# Heracles_Headers.net
KiCad netlist of a schematic drawn in Altium Designer
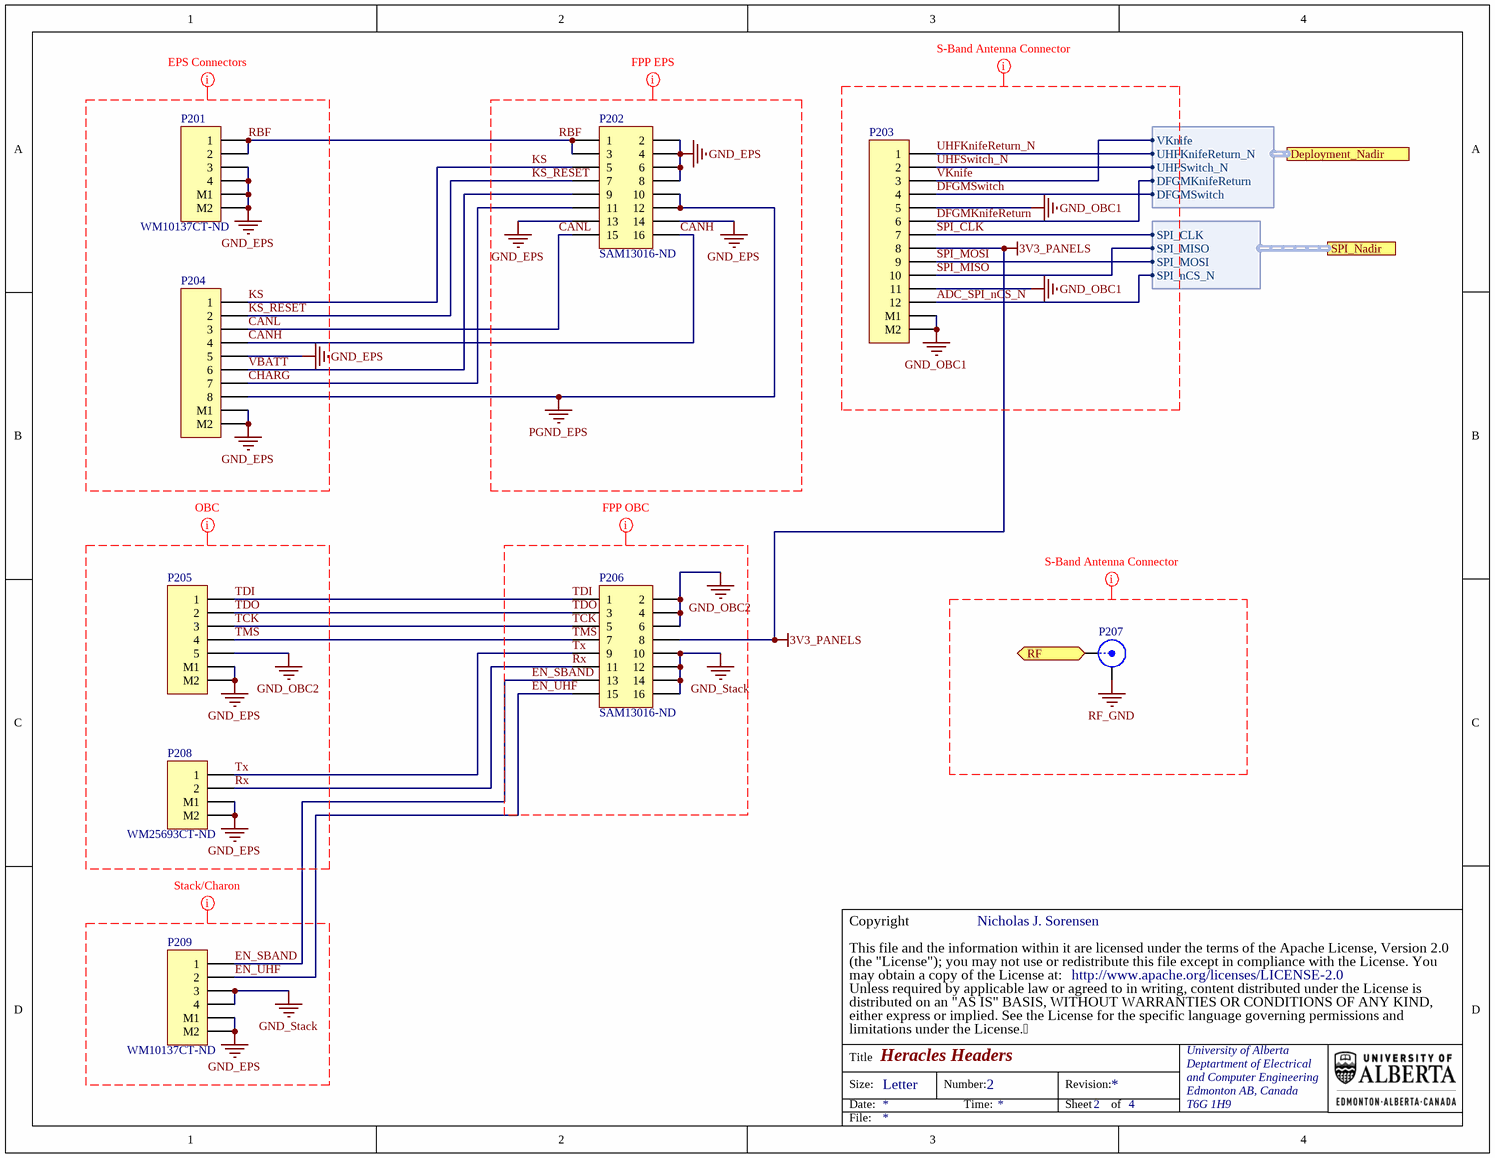
[diagram p0: Heracles Headers.SchDoc]

(export (version "E")
  (design (tool "Eeschema 10.0.6"))
  (components
    (comp (ref "P201")
      (value "WM10137CT-ND")
      (footprint "MOLX-5040500491")
      (description "CONN HEADER SMD R/A 4POS 1.5MM")
      (fields
        (field (name "PART NUMBER") "63")
        (field (name "MANUFACTURER PART NUMBER") "5040500491")
        (field (name "PUBLISHER") "Altium Limited")
      )
      (libsource (lib "Database") (part "Header 6"))
    )
    (comp (ref "P202")
      (value "SAM13016-ND")
      (footprint "TSS-108-01-G-D")
      (description "CONN HEADER VERT 16POS 2.54MM")
      (fields
        (field (name "PART NUMBER") "PP-SAM-00007")
        (field (name "MANUFACTURER PART NUMBER") "TSS-108-01-G-D")
        (field (name "PUBLISHER") "AlbertaSat")
      )
      (libsource (lib "Database") (part "Header 8X2"))
    )
    (comp (ref "P203")
      (value "PICOLOCK 12")
      (footprint "MOLX-5040501291")
      (description "CONN HEADER SMD R/A 12POS 1.5MM")
      (fields
        (field (name "PART NUMBER") "71")
        (field (name "MANUFACTURER PART NUMBER") "5040501291")
        (field (name "PUBLISHER") "Altium Limited")
      )
      (libsource (lib "Database") (part "Header 14"))
    )
    (comp (ref "P204")
      (value "WM14421CT-ND")
      (footprint "MOLX-5040500891")
      (description "CONN HEADER SMD R/A 8POS 1.5MM")
      (fields
        (field (name "PART NUMBER") "67")
        (field (name "MANUFACTURER PART NUMBER") "5040500891")
        (field (name "PUBLISHER") "Altium Limited")
      )
      (libsource (lib "Database") (part "Header 10"))
    )
    (comp (ref "P205")
      (value "PICOLOCK 5")
      (footprint "MOLX-5040500591")
      (description "CONN HEADER SMD R/A 5POS 1.5MM")
      (fields
        (field (name "PART NUMBER") "64")
        (field (name "MANUFACTURER PART NUMBER") "5040500591")
        (field (name "PUBLISHER") "Altium Limited")
      )
      (libsource (lib "Database") (part "Header 7"))
    )
    (comp (ref "P206")
      (value "SAM13016-ND")
      (footprint "TSS-108-01-G-D")
      (description "CONN HEADER VERT 16POS 2.54MM")
      (fields
        (field (name "PART NUMBER") "PP-SAM-00007")
        (field (name "MANUFACTURER PART NUMBER") "TSS-108-01-G-D")
        (field (name "PUBLISHER") "AlbertaSat")
      )
      (libsource (lib "Database") (part "Header 8X2"))
    )
    (comp (ref "P207")
      (value "J10399-ND")
      (footprint "J10399-ND")
      (description "CONN SMB PLUG R/A 50OHM PCB")
      (fields
        (field (name "PART NUMBER") "P01-CIN-00000")
        (field (name "MANUFACTURER PART NUMBER") "Cinch Connectivity Solutions Johnson")
        (field (name "PUBLISHER") "AlbertaSat")
      )
      (libsource (lib "Database") (part "SMB"))
    )
    (comp (ref "P208")
      (value "WM25693CT-ND")
      (footprint "MOLX-5040500291")
      (description "CONN HEADER SMD R/A 2POS 1.5MM")
      (fields
        (field (name "PART NUMBER") "61")
        (field (name "MANUFACTURER PART NUMBER") "5040500291")
        (field (name "PUBLISHER") "Altium Limited")
      )
      (libsource (lib "Database") (part "Header 4"))
    )
    (comp (ref "P209")
      (value "WM10137CT-ND")
      (footprint "MOLX-5040500491")
      (description "CONN HEADER SMD R/A 4POS 1.5MM")
      (fields
        (field (name "PART NUMBER") "63")
        (field (name "MANUFACTURER PART NUMBER") "5040500491")
        (field (name "PUBLISHER") "Altium Limited")
      )
      (libsource (lib "Database") (part "Header 6"))
    )
  )
  (nets
    (net (code "3") (name "/ADC_SPI_nCS_N") (class "Default")
      (node (ref "P203") (pin "12") (pinfunction "12_12") (pintype "passive"))
    )
    (net (code "4") (name "/CANH") (class "Default")
      (node (ref "P202") (pin "16") (pinfunction "16_16") (pintype "passive"))
      (node (ref "P204") (pin "4") (pinfunction "4_4") (pintype "passive"))
    )
    (net (code "5") (name "/CANL") (class "Default")
      (node (ref "P202") (pin "15") (pinfunction "15_15") (pintype "passive"))
      (node (ref "P204") (pin "3") (pinfunction "3_3") (pintype "passive"))
    )
    (net (code "6") (name "/CHARG") (class "Default")
      (node (ref "P202") (pin "11") (pinfunction "11_11") (pintype "passive"))
      (node (ref "P204") (pin "7") (pinfunction "7_7") (pintype "passive"))
    )
    (net (code "7") (name "/DFGMKnifeReturn") (class "Default")
      (node (ref "P203") (pin "6") (pinfunction "6_6") (pintype "passive"))
    )
    (net (code "8") (name "/DFGMSwitch") (class "Default")
      (node (ref "P203") (pin "4") (pinfunction "4_4") (pintype "passive"))
    )
    (net (code "9") (name "/EN_SBAND") (class "Default")
      (node (ref "P206") (pin "13") (pinfunction "13_13") (pintype "passive"))
      (node (ref "P209") (pin "1") (pinfunction "1_1") (pintype "passive"))
    )
    (net (code "10") (name "/EN_UHF") (class "Default")
      (node (ref "P206") (pin "15") (pinfunction "15_15") (pintype "passive"))
      (node (ref "P209") (pin "2") (pinfunction "2_2") (pintype "passive"))
    )
    (net (code "11") (name "/KS") (class "Default")
      (node (ref "P202") (pin "5") (pinfunction "5_5") (pintype "passive"))
      (node (ref "P204") (pin "1") (pinfunction "1_1") (pintype "passive"))
    )
    (net (code "12") (name "/KS_RESET") (class "Default")
      (node (ref "P202") (pin "7") (pinfunction "7_7") (pintype "passive"))
      (node (ref "P204") (pin "2") (pinfunction "2_2") (pintype "passive"))
    )
    (net (code "13") (name "/RBF") (class "Default")
      (node (ref "P201") (pin "1") (pinfunction "1_1") (pintype "passive"))
      (node (ref "P201") (pin "2") (pinfunction "2_2") (pintype "passive"))
      (node (ref "P202") (pin "1") (pinfunction "1_1") (pintype "passive"))
      (node (ref "P202") (pin "3") (pinfunction "3_3") (pintype "passive"))
    )
    (net (code "14") (name "/RF") (class "Default")
      (node (ref "P207") (pin "1") (pinfunction "X_1") (pintype "passive"))
    )
    (net (code "15") (name "/Rx") (class "Default")
      (node (ref "P206") (pin "11") (pinfunction "11_11") (pintype "passive"))
      (node (ref "P208") (pin "2") (pinfunction "2_2") (pintype "passive"))
    )
    (net (code "16") (name "/SPI_CLK") (class "Default")
      (node (ref "P203") (pin "7") (pinfunction "7_7") (pintype "passive"))
    )
    (net (code "17") (name "/SPI_MISO") (class "Default")
      (node (ref "P203") (pin "10") (pinfunction "10_10") (pintype "passive"))
    )
    (net (code "18") (name "/SPI_MOSI") (class "Default")
      (node (ref "P203") (pin "9") (pinfunction "9_9") (pintype "passive"))
    )
    (net (code "19") (name "/TCK") (class "Default")
      (node (ref "P205") (pin "3") (pinfunction "3_3") (pintype "passive"))
      (node (ref "P206") (pin "5") (pinfunction "5_5") (pintype "passive"))
    )
    (net (code "20") (name "/TDI") (class "Default")
      (node (ref "P205") (pin "1") (pinfunction "1_1") (pintype "passive"))
      (node (ref "P206") (pin "1") (pinfunction "1_1") (pintype "passive"))
    )
    (net (code "21") (name "/TDO") (class "Default")
      (node (ref "P205") (pin "2") (pinfunction "2_2") (pintype "passive"))
      (node (ref "P206") (pin "3") (pinfunction "3_3") (pintype "passive"))
    )
    (net (code "22") (name "/TMS") (class "Default")
      (node (ref "P205") (pin "4") (pinfunction "4_4") (pintype "passive"))
      (node (ref "P206") (pin "7") (pinfunction "7_7") (pintype "passive"))
    )
    (net (code "23") (name "/Tx") (class "Default")
      (node (ref "P206") (pin "9") (pinfunction "9_9") (pintype "passive"))
      (node (ref "P208") (pin "1") (pinfunction "1_1") (pintype "passive"))
    )
    (net (code "24") (name "/UHFKnifeReturn_N") (class "Default")
      (node (ref "P203") (pin "1") (pinfunction "1_1") (pintype "passive"))
    )
    (net (code "25") (name "/UHFSwitch_N") (class "Default")
      (node (ref "P203") (pin "2") (pinfunction "2_2") (pintype "passive"))
    )
    (net (code "26") (name "/VBATT") (class "Default")
      (node (ref "P202") (pin "9") (pinfunction "9_9") (pintype "passive"))
      (node (ref "P204") (pin "6") (pinfunction "6_6") (pintype "passive"))
    )
    (net (code "27") (name "/VKnife") (class "Default")
      (node (ref "P203") (pin "3") (pinfunction "3_3") (pintype "passive"))
    )
    (net (code "30") (name "3V3_PANELS") (class "Default")
      (node (ref "P203") (pin "8") (pinfunction "8_8") (pintype "passive"))
      (node (ref "P206") (pin "8") (pinfunction "8_8") (pintype "passive"))
    )
    (net (code "31") (name "GND_EPS") (class "Default")
      (node (ref "P201") (pin "3") (pinfunction "3_3") (pintype "passive"))
      (node (ref "P201") (pin "4") (pinfunction "4_4") (pintype "passive"))
      (node (ref "P201") (pin "M1") (pinfunction "M1_M1") (pintype "passive"))
      (node (ref "P201") (pin "M2") (pinfunction "M2_M2") (pintype "passive"))
      (node (ref "P202") (pin "13") (pinfunction "13_13") (pintype "passive"))
      (node (ref "P202") (pin "14") (pinfunction "14_14") (pintype "passive"))
      (node (ref "P202") (pin "2") (pinfunction "2_2") (pintype "passive"))
      (node (ref "P202") (pin "4") (pinfunction "4_4") (pintype "passive"))
      (node (ref "P202") (pin "6") (pinfunction "6_6") (pintype "passive"))
      (node (ref "P202") (pin "8") (pinfunction "8_8") (pintype "passive"))
      (node (ref "P204") (pin "5") (pinfunction "5_5") (pintype "passive"))
      (node (ref "P204") (pin "M1") (pinfunction "M1_M1") (pintype "passive"))
      (node (ref "P204") (pin "M2") (pinfunction "M2_M2") (pintype "passive"))
      (node (ref "P205") (pin "M1") (pinfunction "M1_M1") (pintype "passive"))
      (node (ref "P205") (pin "M2") (pinfunction "M2_M2") (pintype "passive"))
      (node (ref "P208") (pin "M1") (pinfunction "M1_M1") (pintype "passive"))
      (node (ref "P208") (pin "M2") (pinfunction "M2_M2") (pintype "passive"))
      (node (ref "P209") (pin "M1") (pinfunction "M1_M1") (pintype "passive"))
      (node (ref "P209") (pin "M2") (pinfunction "M2_M2") (pintype "passive"))
    )
    (net (code "32") (name "GND_OBC1") (class "Default")
      (node (ref "P203") (pin "11") (pinfunction "11_11") (pintype "passive"))
      (node (ref "P203") (pin "5") (pinfunction "5_5") (pintype "passive"))
      (node (ref "P203") (pin "M1") (pinfunction "M1_M1") (pintype "passive"))
      (node (ref "P203") (pin "M2") (pinfunction "M2_M2") (pintype "passive"))
    )
    (net (code "33") (name "GND_OBC2") (class "Default")
      (node (ref "P205") (pin "5") (pinfunction "5_5") (pintype "passive"))
      (node (ref "P206") (pin "2") (pinfunction "2_2") (pintype "passive"))
      (node (ref "P206") (pin "4") (pinfunction "4_4") (pintype "passive"))
      (node (ref "P206") (pin "6") (pinfunction "6_6") (pintype "passive"))
    )
    (net (code "34") (name "GND_Stack") (class "Default")
      (node (ref "P206") (pin "10") (pinfunction "10_10") (pintype "passive"))
      (node (ref "P206") (pin "12") (pinfunction "12_12") (pintype "passive"))
      (node (ref "P206") (pin "14") (pinfunction "14_14") (pintype "passive"))
      (node (ref "P206") (pin "16") (pinfunction "16_16") (pintype "passive"))
      (node (ref "P209") (pin "3") (pinfunction "3_3") (pintype "passive"))
      (node (ref "P209") (pin "4") (pinfunction "4_4") (pintype "passive"))
    )
    (net (code "35") (name "PGND_EPS") (class "Default")
      (node (ref "P202") (pin "10") (pinfunction "10_10") (pintype "passive"))
      (node (ref "P202") (pin "12") (pinfunction "12_12") (pintype "passive"))
      (node (ref "P204") (pin "8") (pinfunction "8_8") (pintype "passive"))
    )
    (net (code "36") (name "RF_GND") (class "Default")
      (node (ref "P207") (pin "2") (pinfunction "Y_2") (pintype "passive"))
    )
  )
)
